# mainboard.net
KiCad netlist of a schematic drawn in Altium Designer
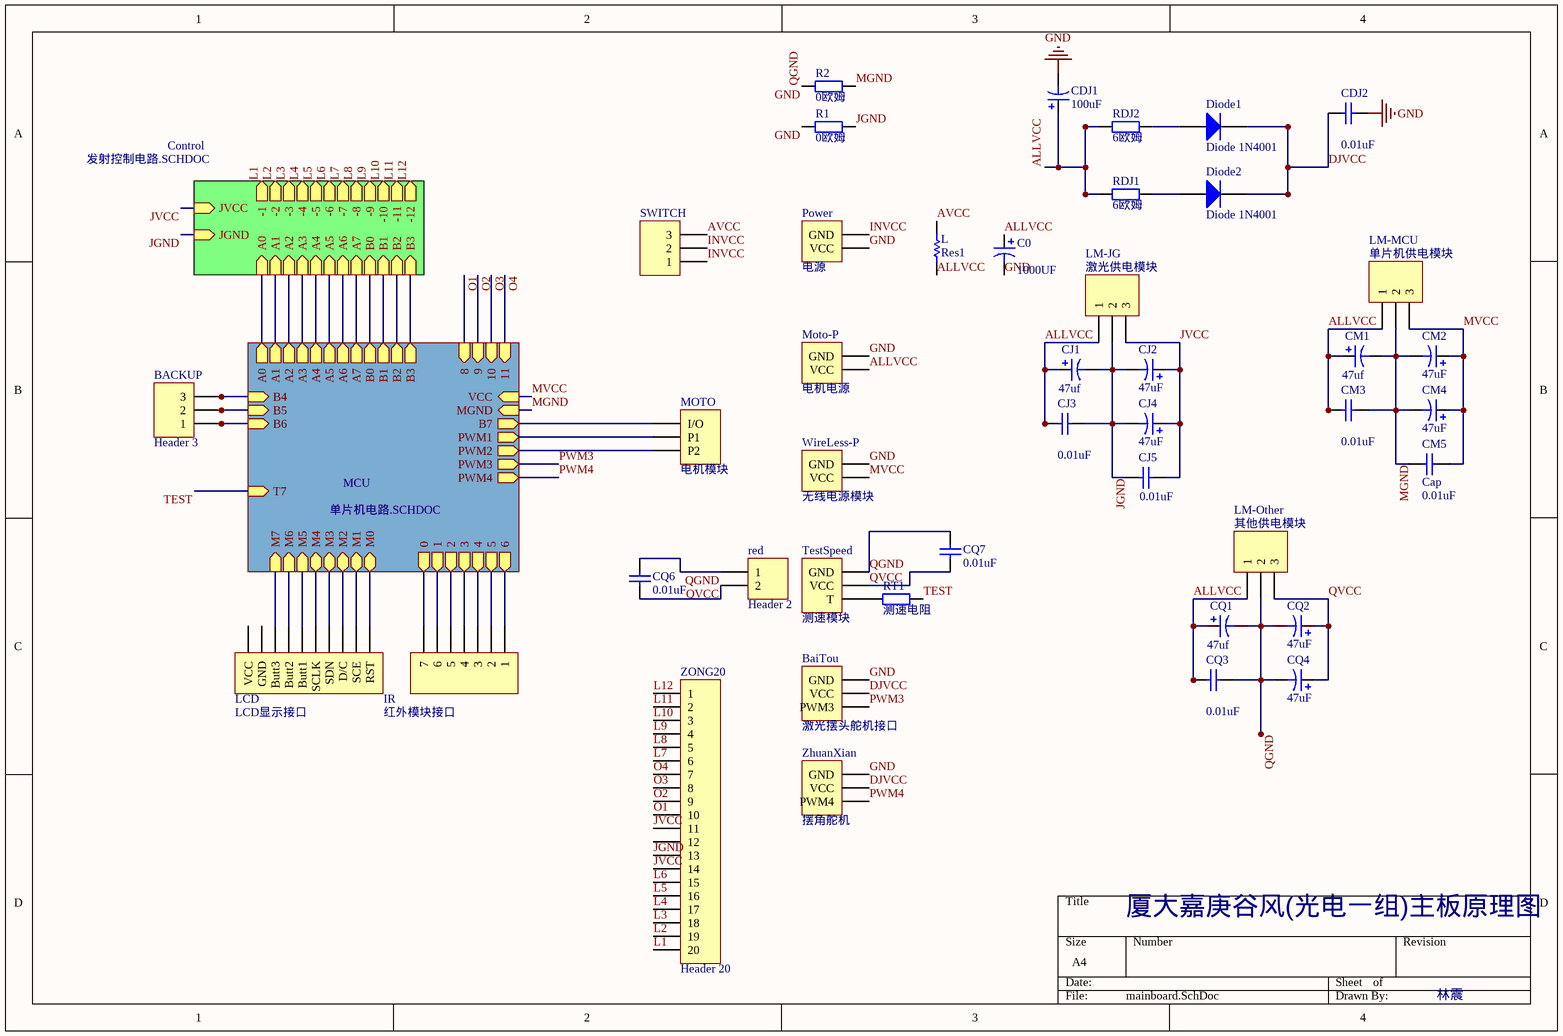
[diagram p0: mainboard.SchDoc]

(export (version "E")
  (design (tool "Eeschema 10.0.6"))
  (components
    (comp (ref "BACKUP")
      (value "Header 3")
      (footprint "HDR1X3")
      (description "备用")
      (fields (field (name "PUBLISHER") "Altium Limited"))
      (libsource (lib "Miscellaneous Connectors") (part "Header 3"))
    )
    (comp (ref "BaiTou")
      (value "激光摆头舵机接口")
      (footprint "HDR1X3")
      (description "Header, 3-Pin")
      (fields (field (name "PUBLISHER") "Altium Limited"))
      (libsource (lib "") (part "Header 3_4"))
    )
    (comp (ref "C0")
      (value "1000UF")
      (footprint "1000UF")
      (description "Polarized Capacitor (Surface Mount)")
      (fields (field (name "Comment") "BATT") (field (name "PUBLISHER") "Altium Limited"))
      (libsource (lib "Miscellaneous Devices") (part "Cap Pol3"))
    )
    (comp (ref "CDJ1")
      (value "100uF")
      (footprint "100UF")
      (description "Polarized Capacitor (Radial)")
      (fields (field (name "PUBLISHER") "Altium Limited"))
      (libsource (lib "Miscellaneous Devices") (part "Cap Pol1"))
    )
    (comp (ref "CDJ2")
      (value "0.01uF")
      (footprint "mainLib:0805")
      (description "Capacitor")
      (fields (field (name "Comment") "Cap") (field (name "PUBLISHER") "Altium Limited"))
      (libsource (lib "Miscellaneous Devices") (part "Cap"))
    )
    (comp (ref "CJ1")
      (value "47uf")
      (footprint "mainLib:3528")
      (description "Polarized Capacitor (Surface Mount)")
      (fields (field (name "Comment") "Cap Pol3") (field (name "PUBLISHER") "Altium Limited"))
      (libsource (lib "Miscellaneous Devices") (part "Cap Pol3"))
    )
    (comp (ref "CJ2")
      (value "47uF")
      (footprint "mainLib:3528")
      (description "Polarized Capacitor (Radial)")
      (fields (field (name "PUBLISHER") "Altium Limited"))
      (libsource (lib "Miscellaneous Devices") (part "Cap Pol1"))
    )
    (comp (ref "CJ3")
      (value "0.01uF")
      (footprint "mainLib:0805")
      (description "Capacitor")
      (fields (field (name "Comment") "Cap") (field (name "PUBLISHER") "Altium Limited"))
      (libsource (lib "Miscellaneous Devices") (part "Cap"))
    )
    (comp (ref "CJ4")
      (value "47uF")
      (footprint "mainLib:47UF")
      (description "Polarized Capacitor (Radial)")
      (fields (field (name "PUBLISHER") "Altium Limited"))
      (libsource (lib "Miscellaneous Devices") (part "Cap Pol1"))
    )
    (comp (ref "CJ5")
      (value "0.01uF")
      (footprint "mainLib:0805")
      (description "Capacitor")
      (fields (field (name "Comment") "Cap") (field (name "PUBLISHER") "Altium Limited"))
      (libsource (lib "Miscellaneous Devices") (part "Cap"))
    )
    (comp (ref "CM1")
      (value "47uf")
      (footprint "mainLib:3528")
      (description "Polarized Capacitor (Surface Mount)")
      (fields (field (name "Comment") "Cap Pol3") (field (name "PUBLISHER") "Altium Limited"))
      (libsource (lib "Miscellaneous Devices") (part "Cap Pol3"))
    )
    (comp (ref "CM2")
      (value "47uF")
      (footprint "mainLib:3528")
      (description "Polarized Capacitor (Radial)")
      (fields (field (name "PUBLISHER") "Altium Limited"))
      (libsource (lib "Miscellaneous Devices") (part "Cap Pol1"))
    )
    (comp (ref "CM3")
      (value "0.01uF")
      (footprint "mainLib:0805")
      (description "Capacitor")
      (fields (field (name "Comment") "Cap") (field (name "PUBLISHER") "Altium Limited"))
      (libsource (lib "Miscellaneous Devices") (part "Cap"))
    )
    (comp (ref "CM4")
      (value "47uF")
      (footprint "mainLib:47UF")
      (description "Polarized Capacitor (Radial)")
      (fields (field (name "PUBLISHER") "Altium Limited"))
      (libsource (lib "Miscellaneous Devices") (part "Cap Pol1"))
    )
    (comp (ref "CM5")
      (value "Cap")
      (footprint "mainLib:0805")
      (description "Capacitor")
      (fields (field (name "ALTIUM_VALUE") "0.01uF") (field (name "PUBLISHER") "Altium Limited"))
      (libsource (lib "Miscellaneous Devices") (part "Cap"))
    )
    (comp (ref "CQ1")
      (value "47uf")
      (footprint "mainLib:3528")
      (description "Polarized Capacitor (Surface Mount)")
      (fields (field (name "Comment") "Cap Pol3") (field (name "PUBLISHER") "Altium Limited"))
      (libsource (lib "Miscellaneous Devices") (part "Cap Pol3"))
    )
    (comp (ref "CQ2")
      (value "47uF")
      (footprint "mainLib:3528")
      (description "Polarized Capacitor (Radial)")
      (fields (field (name "PUBLISHER") "Altium Limited"))
      (libsource (lib "Miscellaneous Devices") (part "Cap Pol1"))
    )
    (comp (ref "CQ3")
      (value "0.01uF")
      (footprint "mainLib:0805")
      (description "Capacitor")
      (fields (field (name "Comment") "Cap") (field (name "PUBLISHER") "Altium Limited"))
      (libsource (lib "Miscellaneous Devices") (part "Cap"))
    )
    (comp (ref "CQ4")
      (value "47uF")
      (footprint "mainLib:47UF")
      (description "Polarized Capacitor (Radial)")
      (fields (field (name "PUBLISHER") "Altium Limited"))
      (libsource (lib "Miscellaneous Devices") (part "Cap Pol1"))
    )
    (comp (ref "CQ6")
      (value "0.01uF")
      (footprint "mainLib:0805")
      (description "Capacitor")
      (fields (field (name "Comment") "Cap") (field (name "PUBLISHER") "Altium Limited"))
      (libsource (lib "Miscellaneous Devices") (part "Cap"))
    )
    (comp (ref "CQ7")
      (value "0.01uF")
      (footprint "mainLib:0805")
      (description "Capacitor")
      (fields (field (name "Comment") "Cap") (field (name "PUBLISHER") "Altium Limited"))
      (libsource (lib "Miscellaneous Devices") (part "Cap"))
    )
    (comp (ref "Diode1")
      (value "Diode 1N4001")
      (footprint "DO-41")
      (description "1 Amp General Purpose Rectifier")
      (fields (field (name "PUBLISHER") "Altium Limited"))
      (libsource (lib "Miscellaneous Devices") (part "Diode 1N4001"))
    )
    (comp (ref "Diode2")
      (value "Diode 1N4001")
      (footprint "DO-41")
      (description "1 Amp General Purpose Rectifier")
      (fields (field (name "PUBLISHER") "Altium Limited"))
      (libsource (lib "Miscellaneous Devices") (part "Diode 1N4001"))
    )
    (comp (ref "IR")
      (value "红外模块接口")
      (footprint "HDR1X7")
      (description "Header, 7-Pin")
      (fields (field (name "PUBLISHER") "Altium Limited"))
      (libsource (lib "Miscellaneous Connectors") (part "Header 7"))
    )
    (comp (ref "L")
      (value "Res1")
      (footprint "10UH")
      (description "Resistor")
      (fields (field (name "PUBLISHER") "Altium Limited"))
      (libsource (lib "Miscellaneous Devices") (part "Res1"))
    )
    (comp (ref "LCD")
      (value "LCD显示接口")
      (footprint "HDR1X10")
      (description "Header, 10-Pin")
      (fields (field (name "PUBLISHER") "Altium Limited"))
      (libsource (lib "Miscellaneous Connectors") (part "Header 10"))
    )
    (comp (ref "LM-JG")
      (value "激光供电模块")
      (footprint "HDR1X3")
      (description "Header, 3-Pin")
      (fields (field (name "PUBLISHER") "Altium Limited"))
      (libsource (lib "") (part "Header 3_2"))
    )
    (comp (ref "LM-MCU")
      (value "单片机供电模块")
      (footprint "HDR1X3")
      (description "Header, 3-Pin")
      (fields (field (name "PUBLISHER") "Altium Limited"))
      (libsource (lib "") (part "Header 3_2"))
    )
    (comp (ref "LM-Other")
      (value "其他供电模块")
      (footprint "HDR1X3")
      (description "Header, 3-Pin")
      (fields (field (name "PUBLISHER") "Altium Limited"))
      (libsource (lib "") (part "Header 3_2"))
    )
    (comp (ref "MOTO")
      (value "电机模块")
      (footprint "HDR1X3")
      (description "Header, 3-Pin")
      (fields (field (name "PUBLISHER") "Altium Limited"))
      (libsource (lib "") (part "Header 3_5"))
    )
    (comp (ref "Moto-P")
      (value "电机电源")
      (footprint "tongzhu")
      (description "Header, 2-Pin")
      (fields (field (name "PUBLISHER") "Altium Limited"))
      (libsource (lib "") (part "Header 2_1"))
    )
    (comp (ref "Power")
      (value "电源")
      (footprint "tongzhu")
      (description "Header, 2-Pin")
      (fields (field (name "PUBLISHER") "Altium Limited"))
      (libsource (lib "") (part "Header 2_1"))
    )
    (comp (ref "R1")
      (value "0欧姆")
      (footprint "0805")
      (description "Resistor")
      (fields (field (name "PUBLISHER") "Altium Limited"))
      (libsource (lib "Miscellaneous Devices") (part "Res2"))
    )
    (comp (ref "R2")
      (value "0欧姆")
      (footprint "0805")
      (description "Resistor")
      (fields (field (name "PUBLISHER") "Altium Limited"))
      (libsource (lib "Miscellaneous Devices") (part "Res2"))
    )
    (comp (ref "RDJ1")
      (value "6欧姆")
      (footprint "0805")
      (description "Resistor")
      (fields (field (name "PUBLISHER") "Altium Limited"))
      (libsource (lib "Miscellaneous Devices") (part "Res2"))
    )
    (comp (ref "RDJ2")
      (value "6欧姆")
      (footprint "0805")
      (description "Resistor")
      (fields (field (name "PUBLISHER") "Altium Limited"))
      (libsource (lib "Miscellaneous Devices") (part "Res2"))
    )
    (comp (ref "red")
      (value "Header 2")
      (footprint "HDR1X2")
      (description "Header, 2-Pin")
      (fields (field (name "PUBLISHER") "Altium Limited"))
      (libsource (lib "Miscellaneous Connectors") (part "Header 2"))
    )
    (comp (ref "RT1")
      (value "测速电阻")
      (footprint "0805")
      (description "Resistor")
      (fields (field (name "PUBLISHER") "Altium Limited"))
      (libsource (lib "") (part "Res2_1"))
    )
    (comp (ref "SWITCH")
      (value "SWITCH")
      (footprint "SWITCH")
      (description "Header, 3-Pin")
      (fields (field (name "PUBLISHER") "Altium Limited"))
      (libsource (lib "Miscellaneous Connectors") (part "Header 3"))
    )
    (comp (ref "TestSpeed")
      (value "测速模块")
      (footprint "HDR1X3")
      (description "Header, 3-Pin")
      (fields (field (name "PUBLISHER") "Altium Limited"))
      (libsource (lib "") (part "Header 3_1"))
    )
    (comp (ref "WireLess-P")
      (value "无线电源模块")
      (footprint "HDR1X2")
      (description "Header, 2-Pin")
      (fields (field (name "PUBLISHER") "Altium Limited"))
      (libsource (lib "") (part "Header 2_1"))
    )
    (comp (ref "ZhuanXian")
      (value "摆角舵机")
      (footprint "HDR1X3")
      (description "Header, 3-Pin")
      (fields (field (name "PUBLISHER") "Altium Limited"))
      (libsource (lib "") (part "Header 3_3"))
    )
    (comp (ref "ZONG20")
      (value "Header 20")
      (footprint "ZONG20")
      (description "传感下来引脚")
      (fields (field (name "PUBLISHER") "Altium Limited"))
      (libsource (lib "Miscellaneous Connectors") (part "Header 20"))
    )
  )
  (nets
    (net (code "1") (name "/0") (class "Default")
      (node (ref "IR") (pin "7") (pinfunction "7_7") (pintype "passive"))
    )
    (net (code "2") (name "/1") (class "Default")
      (node (ref "IR") (pin "6") (pinfunction "6_6") (pintype "passive"))
    )
    (net (code "3") (name "/2") (class "Default")
      (node (ref "IR") (pin "5") (pinfunction "5_5") (pintype "passive"))
    )
    (net (code "4") (name "/3") (class "Default")
      (node (ref "IR") (pin "4") (pinfunction "4_4") (pintype "passive"))
    )
    (net (code "5") (name "/4") (class "Default")
      (node (ref "IR") (pin "3") (pinfunction "3_3") (pintype "passive"))
    )
    (net (code "6") (name "/5") (class "Default")
      (node (ref "IR") (pin "2") (pinfunction "2_2") (pintype "passive"))
    )
    (net (code "7") (name "/6") (class "Default")
      (node (ref "IR") (pin "1") (pinfunction "1_1") (pintype "passive"))
    )
    (net (code "16") (name "/ALLVCC") (class "Default")
      (node (ref "C0") (pin "1") (pinfunction "1_1") (pintype "passive"))
      (node (ref "CDJ1") (pin "1") (pinfunction "1_1") (pintype "passive"))
      (node (ref "CJ1") (pin "1") (pinfunction "1_1") (pintype "passive"))
      (node (ref "CJ3") (pin "2") (pinfunction "2_2") (pintype "passive"))
      (node (ref "CM1") (pin "1") (pinfunction "1_1") (pintype "passive"))
      (node (ref "CM3") (pin "2") (pinfunction "2_2") (pintype "passive"))
      (node (ref "CQ1") (pin "1") (pinfunction "1_1") (pintype "passive"))
      (node (ref "CQ3") (pin "2") (pinfunction "2_2") (pintype "passive"))
      (node (ref "L") (pin "1") (pinfunction "1_1") (pintype "passive"))
      (node (ref "LM-JG") (pin "1") (pinfunction "1_1") (pintype "passive"))
      (node (ref "LM-MCU") (pin "1") (pinfunction "1_1") (pintype "passive"))
      (node (ref "LM-Other") (pin "1") (pinfunction "1_1") (pintype "passive"))
      (node (ref "Moto-P") (pin "1") (pinfunction "VCC_1") (pintype "passive"))
      (node (ref "RDJ1") (pin "2") (pinfunction "2_2") (pintype "passive"))
      (node (ref "RDJ2") (pin "2") (pinfunction "2_2") (pintype "passive"))
    )
    (net (code "17") (name "/AVCC") (class "Default")
      (node (ref "L") (pin "2") (pinfunction "2_2") (pintype "passive"))
      (node (ref "SWITCH") (pin "3") (pinfunction "3_3") (pintype "passive"))
    )
    (net (code "22") (name "/B4") (class "Default")
      (node (ref "BACKUP") (pin "3") (pinfunction "3_3") (pintype "passive"))
    )
    (net (code "23") (name "/B5") (class "Default")
      (node (ref "BACKUP") (pin "2") (pinfunction "2_2") (pintype "passive"))
    )
    (net (code "24") (name "/B6") (class "Default")
      (node (ref "BACKUP") (pin "1") (pinfunction "1_1") (pintype "passive"))
    )
    (net (code "25") (name "/B7") (class "Default")
      (node (ref "MOTO") (pin "1") (pinfunction "I/O_1") (pintype "passive"))
    )
    (net (code "26") (name "/DJVCC") (class "Default")
      (node (ref "BaiTou") (pin "2") (pinfunction "VCC_2") (pintype "passive"))
      (node (ref "CDJ2") (pin "2") (pinfunction "2_2") (pintype "passive"))
      (node (ref "Diode1") (pin "2") (pinfunction "K_2") (pintype "passive"))
      (node (ref "Diode2") (pin "2") (pinfunction "K_2") (pintype "passive"))
      (node (ref "ZhuanXian") (pin "2") (pinfunction "VCC_2") (pintype "passive"))
    )
    (net (code "27") (name "/INVCC") (class "Default")
      (node (ref "Power") (pin "2") (pinfunction "GND_2") (pintype "passive"))
      (node (ref "SWITCH") (pin "1") (pinfunction "1_1") (pintype "passive"))
      (node (ref "SWITCH") (pin "2") (pinfunction "2_2") (pintype "passive"))
    )
    (net (code "28") (name "/JGND") (class "Default")
      (node (ref "CJ1") (pin "2") (pinfunction "2_2") (pintype "passive"))
      (node (ref "CJ2") (pin "2") (pinfunction "2_2") (pintype "passive"))
      (node (ref "CJ3") (pin "1") (pinfunction "1_1") (pintype "passive"))
      (node (ref "CJ4") (pin "2") (pinfunction "2_2") (pintype "passive"))
      (node (ref "CJ5") (pin "2") (pinfunction "2_2") (pintype "passive"))
      (node (ref "LM-JG") (pin "2") (pinfunction "2_2") (pintype "passive"))
      (node (ref "R1") (pin "1") (pinfunction "1_1") (pintype "passive"))
      (node (ref "ZONG20") (pin "13") (pinfunction "13_13") (pintype "passive"))
    )
    (net (code "29") (name "/JVCC") (class "Default")
      (node (ref "CJ2") (pin "1") (pinfunction "1_1") (pintype "passive"))
      (node (ref "CJ4") (pin "1") (pinfunction "1_1") (pintype "passive"))
      (node (ref "CJ5") (pin "1") (pinfunction "1_1") (pintype "passive"))
      (node (ref "LM-JG") (pin "3") (pinfunction "3_3") (pintype "passive"))
      (node (ref "ZONG20") (pin "11") (pinfunction "11_11") (pintype "passive"))
      (node (ref "ZONG20") (pin "14") (pinfunction "14_14") (pintype "passive"))
    )
    (net (code "30") (name "/L1") (class "Default")
      (node (ref "ZONG20") (pin "20") (pinfunction "20_20") (pintype "passive"))
    )
    (net (code "31") (name "/L2") (class "Default")
      (node (ref "ZONG20") (pin "19") (pinfunction "19_19") (pintype "passive"))
    )
    (net (code "32") (name "/L3") (class "Default")
      (node (ref "ZONG20") (pin "18") (pinfunction "18_18") (pintype "passive"))
    )
    (net (code "33") (name "/L4") (class "Default")
      (node (ref "ZONG20") (pin "17") (pinfunction "17_17") (pintype "passive"))
    )
    (net (code "34") (name "/L5") (class "Default")
      (node (ref "ZONG20") (pin "16") (pinfunction "16_16") (pintype "passive"))
    )
    (net (code "35") (name "/L6") (class "Default")
      (node (ref "ZONG20") (pin "15") (pinfunction "15_15") (pintype "passive"))
    )
    (net (code "36") (name "/L7") (class "Default")
      (node (ref "ZONG20") (pin "6") (pinfunction "6_6") (pintype "passive"))
    )
    (net (code "37") (name "/L8") (class "Default")
      (node (ref "ZONG20") (pin "5") (pinfunction "5_5") (pintype "passive"))
    )
    (net (code "38") (name "/L9") (class "Default")
      (node (ref "ZONG20") (pin "4") (pinfunction "4_4") (pintype "passive"))
    )
    (net (code "39") (name "/L10") (class "Default")
      (node (ref "ZONG20") (pin "3") (pinfunction "3_3") (pintype "passive"))
    )
    (net (code "40") (name "/L11") (class "Default")
      (node (ref "ZONG20") (pin "2") (pinfunction "2_2") (pintype "passive"))
    )
    (net (code "41") (name "/L12") (class "Default")
      (node (ref "ZONG20") (pin "1") (pinfunction "1_1") (pintype "passive"))
    )
    (net (code "42") (name "/M0") (class "Default")
      (node (ref "LCD") (pin "1") (pinfunction "RST_1") (pintype "passive"))
    )
    (net (code "43") (name "/M1") (class "Default")
      (node (ref "LCD") (pin "2") (pinfunction "SCE_2") (pintype "passive"))
    )
    (net (code "44") (name "/M2") (class "Default")
      (node (ref "LCD") (pin "3") (pinfunction "D/C_3") (pintype "passive"))
    )
    (net (code "45") (name "/M3") (class "Default")
      (node (ref "LCD") (pin "4") (pinfunction "SDN_4") (pintype "passive"))
    )
    (net (code "46") (name "/M4") (class "Default")
      (node (ref "LCD") (pin "5") (pinfunction "SCLK_5") (pintype "passive"))
    )
    (net (code "47") (name "/M5") (class "Default")
      (node (ref "LCD") (pin "6") (pinfunction "Butt1_6") (pintype "passive"))
    )
    (net (code "48") (name "/M6") (class "Default")
      (node (ref "LCD") (pin "7") (pinfunction "Butt2_7") (pintype "passive"))
    )
    (net (code "49") (name "/M7") (class "Default")
      (node (ref "LCD") (pin "8") (pinfunction "Butt3_8") (pintype "passive"))
    )
    (net (code "50") (name "/MGND") (class "Default")
      (node (ref "CM1") (pin "2") (pinfunction "2_2") (pintype "passive"))
      (node (ref "CM2") (pin "2") (pinfunction "2_2") (pintype "passive"))
      (node (ref "CM3") (pin "1") (pinfunction "1_1") (pintype "passive"))
      (node (ref "CM4") (pin "2") (pinfunction "2_2") (pintype "passive"))
      (node (ref "CM5") (pin "2") (pinfunction "2_2") (pintype "passive"))
      (node (ref "LM-MCU") (pin "2") (pinfunction "2_2") (pintype "passive"))
      (node (ref "R2") (pin "1") (pinfunction "1_1") (pintype "passive"))
    )
    (net (code "51") (name "/MVCC") (class "Default")
      (node (ref "CM2") (pin "1") (pinfunction "1_1") (pintype "passive"))
      (node (ref "CM4") (pin "1") (pinfunction "1_1") (pintype "passive"))
      (node (ref "CM5") (pin "1") (pinfunction "1_1") (pintype "passive"))
      (node (ref "LM-MCU") (pin "3") (pinfunction "3_3") (pintype "passive"))
      (node (ref "WireLess-P") (pin "1") (pinfunction "VCC_1") (pintype "passive"))
    )
    (net (code "52") (name "/O1") (class "Default")
      (node (ref "ZONG20") (pin "10") (pinfunction "10_10") (pintype "passive"))
    )
    (net (code "53") (name "/O2") (class "Default")
      (node (ref "ZONG20") (pin "9") (pinfunction "9_9") (pintype "passive"))
    )
    (net (code "54") (name "/O3") (class "Default")
      (node (ref "ZONG20") (pin "8") (pinfunction "8_8") (pintype "passive"))
    )
    (net (code "55") (name "/O4") (class "Default")
      (node (ref "ZONG20") (pin "7") (pinfunction "7_7") (pintype "passive"))
    )
    (net (code "56") (name "/PWM1") (class "Default")
      (node (ref "MOTO") (pin "2") (pinfunction "P1_2") (pintype "passive"))
    )
    (net (code "57") (name "/PWM2") (class "Default")
      (node (ref "MOTO") (pin "3") (pinfunction "P2_3") (pintype "passive"))
    )
    (net (code "58") (name "/PWM3") (class "Default")
      (node (ref "BaiTou") (pin "1") (pinfunction "PWM3_1") (pintype "passive"))
    )
    (net (code "59") (name "/PWM4") (class "Default")
      (node (ref "ZhuanXian") (pin "1") (pinfunction "PWM4_1") (pintype "passive"))
    )
    (net (code "60") (name "/QVCC") (class "Default")
      (node (ref "CQ2") (pin "1") (pinfunction "1_1") (pintype "passive"))
      (node (ref "CQ4") (pin "1") (pinfunction "1_1") (pintype "passive"))
      (node (ref "CQ6") (pin "2") (pinfunction "2_2") (pintype "passive"))
      (node (ref "CQ7") (pin "2") (pinfunction "2_2") (pintype "passive"))
      (node (ref "LM-Other") (pin "3") (pinfunction "3_3") (pintype "passive"))
      (node (ref "TestSpeed") (pin "2") (pinfunction "VCC_2") (pintype "passive"))
      (node (ref "red") (pin "2") (pinfunction "2_2") (pintype "passive"))
    )
    (net (code "61") (name "/TEST") (class "Default")
      (node (ref "RT1") (pin "2") (pinfunction "2_2") (pintype "passive"))
    )
    (net (code "62") (name "GND") (class "Default")
      (node (ref "BaiTou") (pin "3") (pinfunction "GND_3") (pintype "passive"))
      (node (ref "C0") (pin "2") (pinfunction "2_2") (pintype "passive"))
      (node (ref "CDJ1") (pin "2") (pinfunction "2_2") (pintype "passive"))
      (node (ref "CDJ2") (pin "1") (pinfunction "1_1") (pintype "passive"))
      (node (ref "CQ1") (pin "2") (pinfunction "2_2") (pintype "passive"))
      (node (ref "CQ2") (pin "2") (pinfunction "2_2") (pintype "passive"))
      (node (ref "CQ3") (pin "1") (pinfunction "1_1") (pintype "passive"))
      (node (ref "CQ4") (pin "2") (pinfunction "2_2") (pintype "passive"))
      (node (ref "CQ6") (pin "1") (pinfunction "1_1") (pintype "passive"))
      (node (ref "CQ7") (pin "1") (pinfunction "1_1") (pintype "passive"))
      (node (ref "LM-Other") (pin "2") (pinfunction "2_2") (pintype "passive"))
      (node (ref "Moto-P") (pin "2") (pinfunction "GND_2") (pintype "passive"))
      (node (ref "Power") (pin "1") (pinfunction "VCC_1") (pintype "passive"))
      (node (ref "R1") (pin "2") (pinfunction "2_2") (pintype "passive"))
      (node (ref "R2") (pin "2") (pinfunction "2_2") (pintype "passive"))
      (node (ref "TestSpeed") (pin "3") (pinfunction "GND_3") (pintype "passive"))
      (node (ref "WireLess-P") (pin "2") (pinfunction "GND_2") (pintype "passive"))
      (node (ref "ZhuanXian") (pin "3") (pinfunction "GND_3") (pintype "passive"))
      (node (ref "red") (pin "1") (pinfunction "1_1") (pintype "passive"))
    )
    (net (code "63") (name "Net-(Diode1-A)") (class "Default")
      (node (ref "Diode1") (pin "1") (pinfunction "A_1") (pintype "passive"))
      (node (ref "RDJ2") (pin "1") (pinfunction "1_1") (pintype "passive"))
    )
    (net (code "64") (name "Net-(Diode2-A)") (class "Default")
      (node (ref "Diode2") (pin "1") (pinfunction "A_1") (pintype "passive"))
      (node (ref "RDJ1") (pin "1") (pinfunction "1_1") (pintype "passive"))
    )
    (net (code "65") (name "Net-(TestSpeed-T)") (class "Default")
      (node (ref "RT1") (pin "1") (pinfunction "1_1") (pintype "passive"))
      (node (ref "TestSpeed") (pin "1") (pinfunction "T_1") (pintype "passive"))
    )
    (net (code "66") (name "unconnected-(LCD-GND-Pad9)") (class "Default")
      (node (ref "LCD") (pin "9") (pinfunction "GND_9") (pintype "passive"))
    )
    (net (code "67") (name "unconnected-(LCD-VCC-Pad10)") (class "Default")
      (node (ref "LCD") (pin "10") (pinfunction "VCC_10") (pintype "passive"))
    )
    (net (code "68") (name "unconnected-(ZONG20-Pad12)") (class "Default")
      (node (ref "ZONG20") (pin "12") (pinfunction "12_12") (pintype "passive"))
    )
  )
)
